# RB_AQM_3_NanoGSM.net
KiCad netlist of a schematic drawn in EAGLE
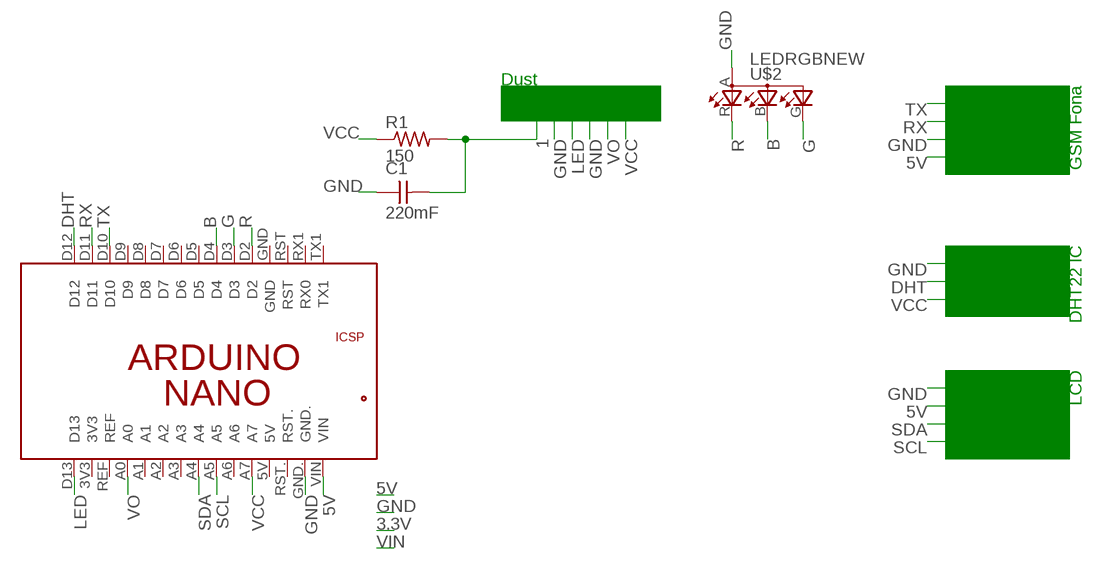
[diagram p0: schematic, sheet 1]

(export (version "E")
  (design (tool "Eeschema 10.0.6"))
  (components
    (comp (ref "C1")
      (value "220mF")
      (footprint "eagle-import:C1206FAB")
      (libsource (lib "eagle-import") (part "CAP-UNPOLARIZEDFAB"))
    )
    (comp (ref "R1")
      (value "150")
      (footprint "eagle-import:R1206FAB")
      (libsource (lib "eagle-import") (part "RES-US1206FAB"))
    )
    (comp (ref "U$2")
      (value "LEDRGBNEW")
      (footprint "eagle-import:P-LCC-4")
      (libsource (lib "eagle-import") (part "LEDRGBNEW"))
    )
    (comp (ref "U$3")
      (value "ARD_NANO")
      (footprint "eagle-import:ARD_NANO")
      (libsource (lib "eagle-import") (part "ARD_NANO"))
    )
  )
  (nets
    (net (code "1") (name "/1") (class "Default")
      (node (ref "C1") (pin "2") (pinfunction "2_2") (pintype "passive"))
      (node (ref "R1") (pin "2") (pinfunction "2_2") (pintype "passive"))
    )
    (net (code "3") (name "/5V") (class "Default")
      (node (ref "U$3") (pin "VIN") (pinfunction "VIN_VIN") (pintype "bidirectional"))
    )
    (net (code "4") (name "/B") (class "Default")
      (node (ref "U$2") (pin "B") (pinfunction "CBLUE_B") (pintype "passive"))
      (node (ref "U$3") (pin "D4") (pinfunction "D4_D4") (pintype "bidirectional"))
    )
    (net (code "5") (name "/DHT") (class "Default")
      (node (ref "U$3") (pin "D12") (pinfunction "D12_D12") (pintype "bidirectional"))
    )
    (net (code "6") (name "/G") (class "Default")
      (node (ref "U$2") (pin "G") (pinfunction "CGREEN_G") (pintype "passive"))
      (node (ref "U$3") (pin "D3") (pinfunction "D3_D3") (pintype "bidirectional"))
    )
    (net (code "7") (name "/GND") (class "Default")
      (node (ref "C1") (pin "1") (pinfunction "1_1") (pintype "passive"))
      (node (ref "U$2") (pin "A") (pinfunction "A2_A") (pintype "passive"))
      (node (ref "U$3") (pin "GND.") (pinfunction "GND._GND.") (pintype "bidirectional"))
    )
    (net (code "8") (name "/LED") (class "Default")
      (node (ref "U$3") (pin "D13") (pinfunction "D13_D13") (pintype "bidirectional"))
    )
    (net (code "9") (name "/R") (class "Default")
      (node (ref "U$2") (pin "R") (pinfunction "CRED_R") (pintype "passive"))
      (node (ref "U$3") (pin "D2") (pinfunction "D2_D2") (pintype "bidirectional"))
    )
    (net (code "10") (name "/RX") (class "Default")
      (node (ref "U$3") (pin "D11") (pinfunction "D11_D11") (pintype "bidirectional"))
    )
    (net (code "11") (name "/SCL") (class "Default")
      (node (ref "U$3") (pin "A5") (pinfunction "A5_A5") (pintype "bidirectional"))
    )
    (net (code "12") (name "/SDA") (class "Default")
      (node (ref "U$3") (pin "A4") (pinfunction "A4_A4") (pintype "bidirectional"))
    )
    (net (code "13") (name "/TX") (class "Default")
      (node (ref "U$3") (pin "D10") (pinfunction "D10_D10") (pintype "bidirectional"))
    )
    (net (code "14") (name "/VCC") (class "Default")
      (node (ref "R1") (pin "1") (pinfunction "1_1") (pintype "passive"))
      (node (ref "U$3") (pin "A7") (pinfunction "A7_A7") (pintype "bidirectional"))
    )
    (net (code "16") (name "/VO") (class "Default")
      (node (ref "U$3") (pin "A0") (pinfunction "A0_A0") (pintype "bidirectional"))
    )
    (net (code "17") (name "unconnected-(U$3-Pad3V3)") (class "Default")
      (node (ref "U$3") (pin "3V3") (pinfunction "3V3_3V3") (pintype "bidirectional"))
    )
    (net (code "18") (name "unconnected-(U$3-Pad5V)") (class "Default")
      (node (ref "U$3") (pin "5V") (pinfunction "5V_5V") (pintype "bidirectional"))
    )
    (net (code "19") (name "unconnected-(U$3-Pad5V.)") (class "Default")
      (node (ref "U$3") (pin "5V.") (pinfunction "5V._5V.") (pintype "bidirectional"))
    )
    (net (code "20") (name "unconnected-(U$3-PadA1)") (class "Default")
      (node (ref "U$3") (pin "A1") (pinfunction "A1_A1") (pintype "bidirectional"))
    )
    (net (code "21") (name "unconnected-(U$3-PadA2)") (class "Default")
      (node (ref "U$3") (pin "A2") (pinfunction "A2_A2") (pintype "bidirectional"))
    )
    (net (code "22") (name "unconnected-(U$3-PadA3)") (class "Default")
      (node (ref "U$3") (pin "A3") (pinfunction "A3_A3") (pintype "bidirectional"))
    )
    (net (code "23") (name "unconnected-(U$3-PadA6)") (class "Default")
      (node (ref "U$3") (pin "A6") (pinfunction "A6_A6") (pintype "bidirectional"))
    )
    (net (code "24") (name "unconnected-(U$3-PadD5)") (class "Default")
      (node (ref "U$3") (pin "D5") (pinfunction "D5_D5") (pintype "bidirectional"))
    )
    (net (code "25") (name "unconnected-(U$3-PadD6)") (class "Default")
      (node (ref "U$3") (pin "D6") (pinfunction "D6_D6") (pintype "bidirectional"))
    )
    (net (code "26") (name "unconnected-(U$3-PadD7)") (class "Default")
      (node (ref "U$3") (pin "D7") (pinfunction "D7_D7") (pintype "bidirectional"))
    )
    (net (code "27") (name "unconnected-(U$3-PadD8)") (class "Default")
      (node (ref "U$3") (pin "D8") (pinfunction "D8_D8") (pintype "bidirectional"))
    )
    (net (code "28") (name "unconnected-(U$3-PadD9)") (class "Default")
      (node (ref "U$3") (pin "D9") (pinfunction "D9_D9") (pintype "bidirectional"))
    )
    (net (code "29") (name "unconnected-(U$3-PadGND)") (class "Default")
      (node (ref "U$3") (pin "GND") (pinfunction "GND_GND") (pintype "bidirectional"))
    )
    (net (code "30") (name "unconnected-(U$3-PadGND_)") (class "Default")
      (node (ref "U$3") (pin "GND_") (pinfunction "GND__GND_") (pintype "bidirectional"))
    )
    (net (code "31") (name "unconnected-(U$3-PadMISO)") (class "Default")
      (node (ref "U$3") (pin "MISO") (pinfunction "MISO_MISO") (pintype "bidirectional"))
    )
    (net (code "32") (name "unconnected-(U$3-PadMOSI)") (class "Default")
      (node (ref "U$3") (pin "MOSI") (pinfunction "MOSI_MOSI") (pintype "bidirectional"))
    )
    (net (code "33") (name "unconnected-(U$3-PadREF)") (class "Default")
      (node (ref "U$3") (pin "REF") (pinfunction "REF_REF") (pintype "bidirectional"))
    )
    (net (code "34") (name "unconnected-(U$3-PadRESET..)") (class "Default")
      (node (ref "U$3") (pin "RESET..") (pinfunction "RESET.._RESET..") (pintype "bidirectional"))
    )
    (net (code "35") (name "unconnected-(U$3-PadRST)") (class "Default")
      (node (ref "U$3") (pin "RST") (pinfunction "RST_RST") (pintype "bidirectional"))
    )
    (net (code "36") (name "unconnected-(U$3-PadRST.)") (class "Default")
      (node (ref "U$3") (pin "RST.") (pinfunction "RST._RST.") (pintype "bidirectional"))
    )
    (net (code "37") (name "unconnected-(U$3-PadSCK)") (class "Default")
      (node (ref "U$3") (pin "SCK") (pinfunction "SCK_SCK") (pintype "bidirectional"))
    )
    (net (code "38") (name "unconnected-(U$3-PadTX1)") (class "Default")
      (node (ref "U$3") (pin "TX1") (pinfunction "TX1_TX1") (pintype "bidirectional"))
    )
    (net (code "39") (name "unconnected-(U$3-RX0-PadRX1)") (class "Default")
      (node (ref "U$3") (pin "RX1") (pinfunction "RX0_RX1") (pintype "bidirectional"))
    )
  )
)
